# Display_Interface.net
KiCad netlist of a schematic drawn in Altium Designer
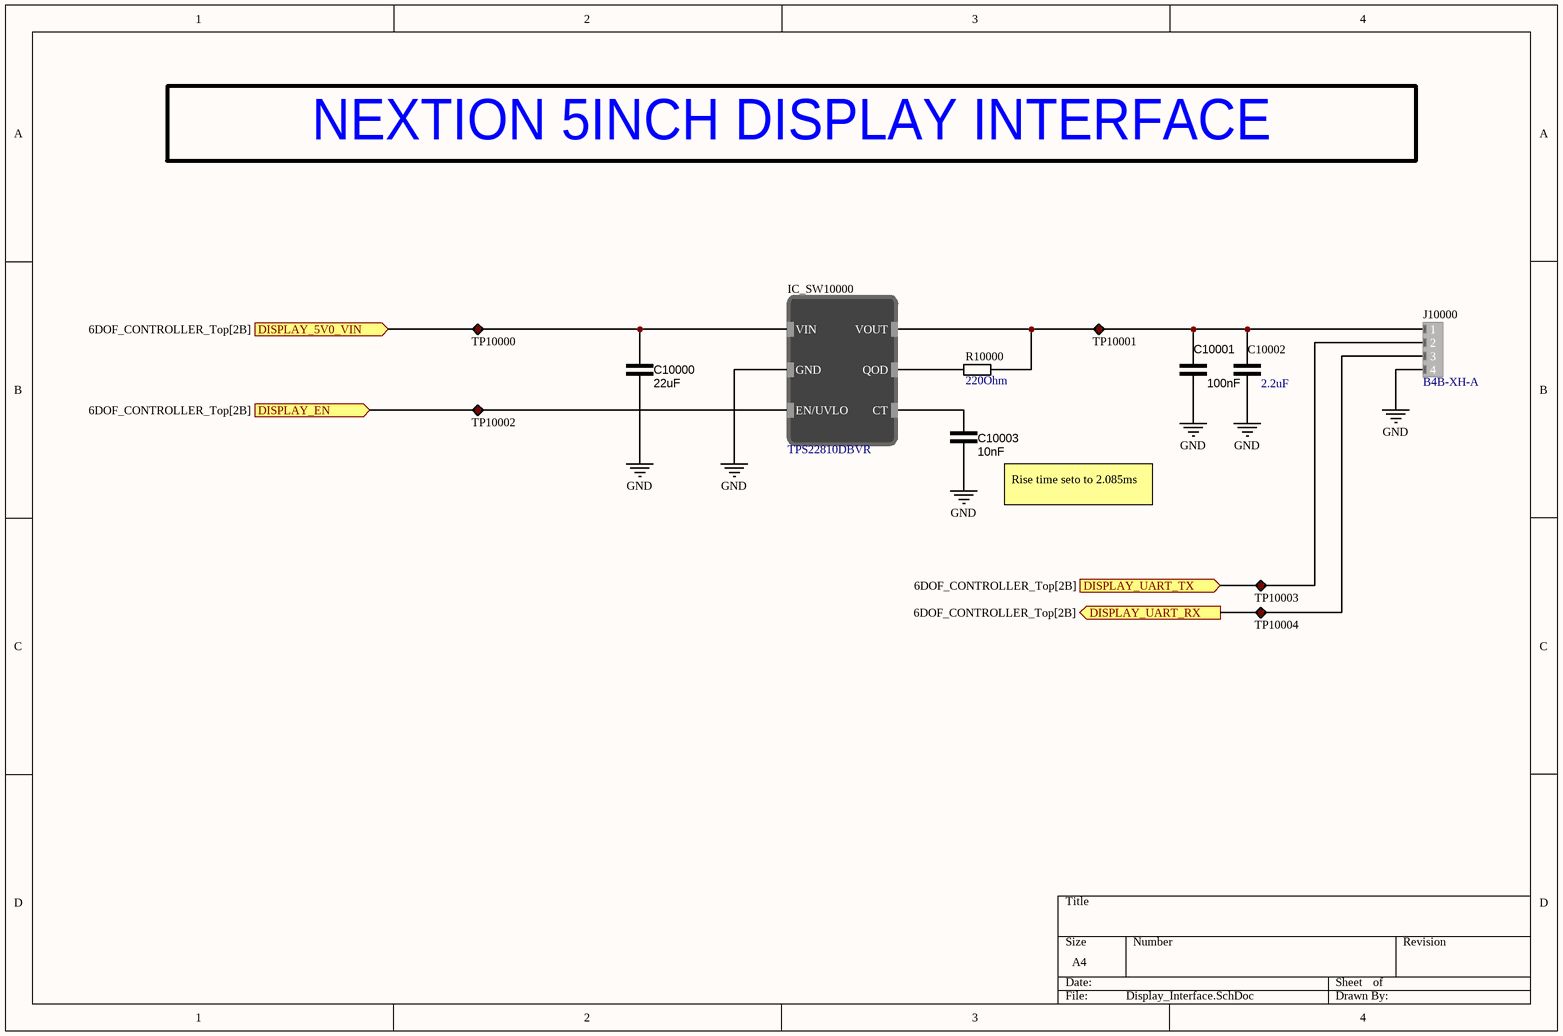
[diagram p0: Display_Interface.SchDoc]

(export (version "E")
  (design (tool "Eeschema 10.0.6"))
  (components
    (comp (ref "C10000")
      (value "22uF")
      (footprint "CAP_0805")
      (description "22 µF ±20% 25V Ceramic Capacitor X5R 0805 (2012 Metric)")
      (fields (field (name "DIGIKEY PART NUMBER") "445-9112-1-ND"))
      (libsource (lib "CapacitorsIntegrated") (part "C000001"))
    )
    (comp (ref "C10001")
      (value "100nF")
      (footprint "CAP_0603")
      (description "0.1 µF ±10% 25V Ceramic Capacitor X7R 0603 (1608 Metric)")
      (fields (field (name "DIGIKEY PART NUMBER") "478-KAM15AR71E104KTCT-ND"))
      (libsource (lib "CapacitorsIntegrated") (part "C000007"))
    )
    (comp (ref "C10002")
      (value "2.2uF")
      (footprint "CAP_0603")
      (description "8 pF ±0.05pF 25V Ceramic Capacitor C0G, NP0 01005 (0402 Metric)")
      (fields (field (name "DIGIKEY PART NUMBER") "490-12731-1-ND"))
      (libsource (lib "CapacitorsIntegrated") (part "C000014"))
    )
    (comp (ref "C10003")
      (value "10nF")
      (footprint "CAP_0603")
      (description "10000 pF ±20% 25V Ceramic Capacitor X7R 0603 (1608 Metric)")
      (fields (field (name "DIGIKEY PART NUMBER") "478-KGM15AR71E103MTCT-ND"))
      (libsource (lib "CapacitorsIntegrated") (part "C000005"))
    )
    (comp (ref "IC_SW10000")
      (value "TPS22810DBVR")
      (footprint "SOT95P280X145-6N")
      (description "Power Switch/Driver 1:1 N-Channel 2A SOT-23-6")
      (fields
        (field (name "DIGIKEY PART NUMBER") "296-45297-1-ND")
        (field (name "MOUSER PART NUMBER") "595-TPS22810DBVR")
      )
      (libsource (lib "IntegratedCircuits") (part "TPS22810"))
    )
    (comp (ref "J10000")
      (value "B4B-XH-A")
      (footprint "JST_XH_4POS")
      (description "Connector Header Through Hole 4 position 0.098\" (2.50mm)")
      (fields (field (name "DIGIKEY PART NUMBER") "455-B4B-XH-A-ND"))
      (libsource (lib "ElectroMechanical") (part "00000014"))
    )
    (comp (ref "R10000")
      (value "220Ohm")
      (footprint "RES_0603")
      (description "220 Ohms ±5% 0.1W, 1/10W Chip Resistor 0603 (1608 Metric) Automotive AEC-Q200 Thick Film")
      (fields (field (name "DIGIKEY PART NUMBER") "P220GCT-ND"))
      (libsource (lib "ResistorsIntegrated") (part "R000021"))
    )
    (comp (ref "TP10000")
      (value "Test point")
      (footprint "TestPoint")
      (description "Test point 1mm")
      (libsource (lib "IntegratedCircuits") (part "TP002"))
    )
    (comp (ref "TP10001")
      (value "Test point")
      (footprint "TestPoint")
      (description "Test point 1mm")
      (libsource (lib "IntegratedCircuits") (part "TP002"))
    )
    (comp (ref "TP10002")
      (value "Test point")
      (footprint "TestPoint")
      (description "Test point 1mm")
      (libsource (lib "IntegratedCircuits") (part "TP002"))
    )
    (comp (ref "TP10003")
      (value "Test point")
      (footprint "TestPoint")
      (description "Test point 1mm")
      (libsource (lib "IntegratedCircuits") (part "TP002"))
    )
    (comp (ref "TP10004")
      (value "Test point")
      (footprint "TestPoint")
      (description "Test point 1mm")
      (libsource (lib "IntegratedCircuits") (part "TP002"))
    )
  )
  (nets
    (net (code "1") (name "/DISPLAY_5V0_VIN") (class "Default")
      (node (ref "C10000") (pin "2") (pinfunction "2_2") (pintype "passive"))
      (node (ref "IC_SW10000") (pin "1") (pinfunction "VIN_1") (pintype "passive"))
      (node (ref "TP10000") (pin "1") (pinfunction "1_1") (pintype "passive"))
    )
    (net (code "2") (name "/DISPLAY_EN") (class "Default")
      (node (ref "IC_SW10000") (pin "3") (pinfunction "EN/UVLO_3") (pintype "passive"))
      (node (ref "TP10002") (pin "1") (pinfunction "1_1") (pintype "passive"))
    )
    (net (code "3") (name "/DISPLAY_UART_RX") (class "Default")
      (node (ref "J10000") (pin "3") (pinfunction "3_3") (pintype "passive"))
      (node (ref "TP10004") (pin "1") (pinfunction "1_1") (pintype "passive"))
    )
    (net (code "4") (name "/DISPLAY_UART_TX") (class "Default")
      (node (ref "J10000") (pin "2") (pinfunction "2_2") (pintype "passive"))
      (node (ref "TP10003") (pin "1") (pinfunction "1_1") (pintype "passive"))
    )
    (net (code "5") (name "GND") (class "Default")
      (node (ref "C10000") (pin "1") (pinfunction "1_1") (pintype "passive"))
      (node (ref "C10001") (pin "2") (pinfunction "2_2") (pintype "passive"))
      (node (ref "C10002") (pin "1") (pinfunction "1_1") (pintype "passive"))
      (node (ref "C10003") (pin "1") (pinfunction "1_1") (pintype "passive"))
      (node (ref "IC_SW10000") (pin "2") (pinfunction "GND_2") (pintype "passive"))
      (node (ref "J10000") (pin "4") (pinfunction "4_4") (pintype "passive"))
    )
    (net (code "6") (name "Net-(IC_SW10000-CT)") (class "Default")
      (node (ref "C10003") (pin "2") (pinfunction "2_2") (pintype "passive"))
      (node (ref "IC_SW10000") (pin "4") (pinfunction "CT_4") (pintype "passive"))
    )
    (net (code "7") (name "Net-(IC_SW10000-QOD)") (class "Default")
      (node (ref "IC_SW10000") (pin "5") (pinfunction "QOD_5") (pintype "passive"))
      (node (ref "R10000") (pin "1") (pinfunction "1_1") (pintype "passive"))
    )
    (net (code "8") (name "Net-(IC_SW10000-VOUT)") (class "Default")
      (node (ref "C10001") (pin "1") (pinfunction "1_1") (pintype "passive"))
      (node (ref "C10002") (pin "2") (pinfunction "2_2") (pintype "passive"))
      (node (ref "IC_SW10000") (pin "6") (pinfunction "VOUT_6") (pintype "passive"))
      (node (ref "J10000") (pin "1") (pinfunction "1_1") (pintype "passive"))
      (node (ref "R10000") (pin "2") (pinfunction "2_2") (pintype "passive"))
      (node (ref "TP10001") (pin "1") (pinfunction "1_1") (pintype "passive"))
    )
  )
)
